# main.net
KiCad netlist of a schematic drawn in EAGLE
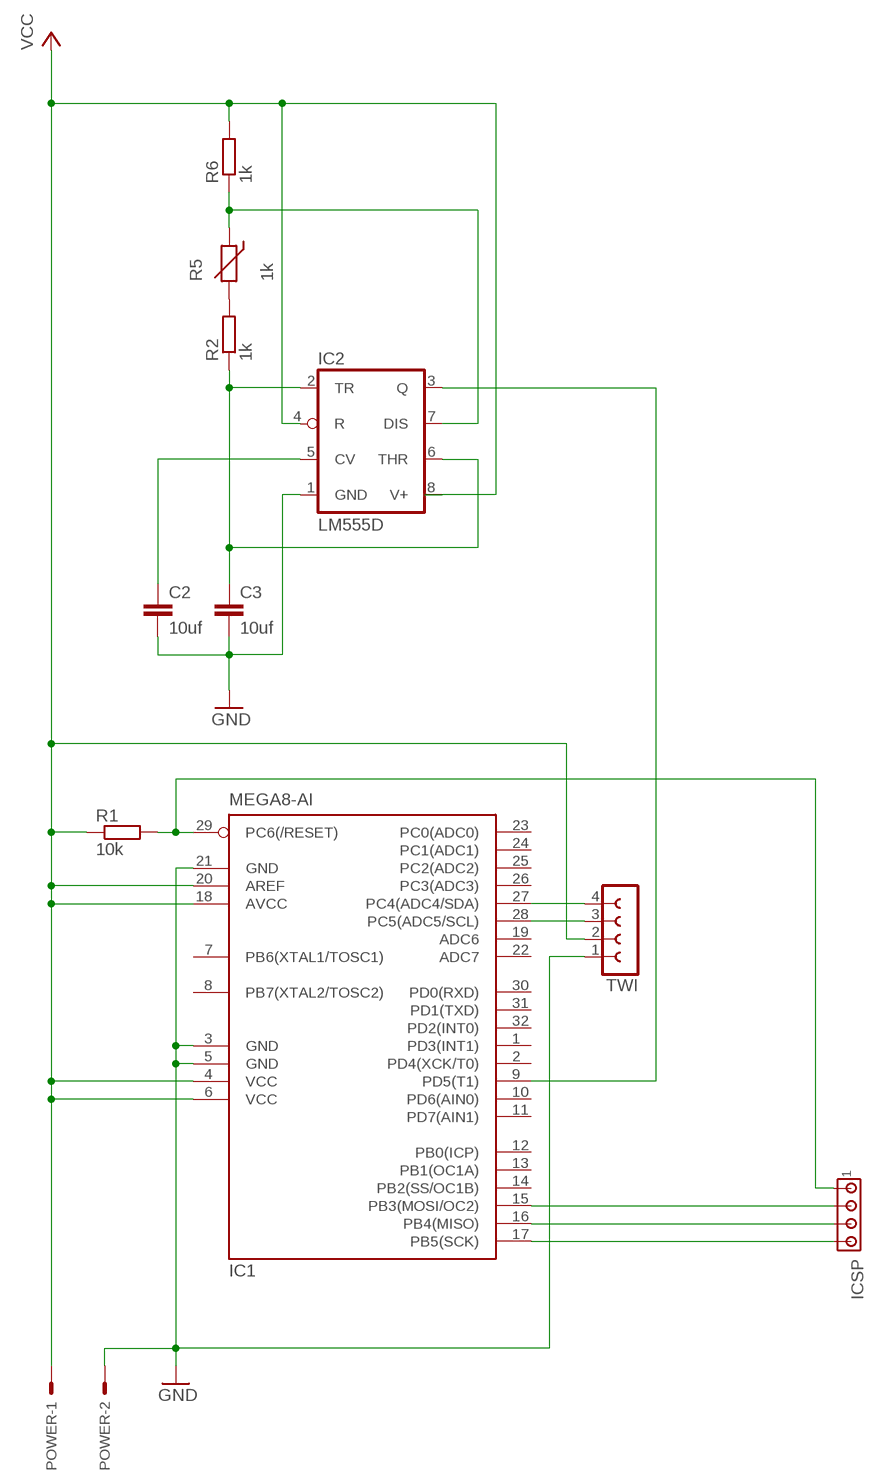
[diagram p0: schematic, sheet 1]

(export (version "E")
  (design (tool "Eeschema 10.0.6"))
  (components
    (comp (ref "C2")
      (value "10uf")
      (footprint "eagle-import:C2012")
      (libsource (lib "eagle-import") (part "C-EUC2012"))
    )
    (comp (ref "C3")
      (value "10uf")
      (footprint "eagle-import:C2012")
      (libsource (lib "eagle-import") (part "C-EUC2012"))
    )
    (comp (ref "IC1")
      (value "MEGA8-AI")
      (footprint "eagle-import:TQFP32-08")
      (fields (field (name "MPN") "ATMEGA8-16AU"))
      (libsource (lib "eagle-import") (part "MEGA8-AI"))
    )
    (comp (ref "IC2")
      (value "LM555D")
      (footprint "eagle-import:SO08")
      (libsource (lib "eagle-import") (part "555DLM"))
    )
    (comp (ref "ICSP")
      (value "MTA04-100")
      (footprint "eagle-import:10X04MTA")
      (libsource (lib "eagle-import") (part "MTA04-100"))
    )
    (comp (ref "POWER")
      (value "332-02")
      (footprint "eagle-import:332-02")
      (libsource (lib "eagle-import") (part "332-02"))
    )
    (comp (ref "R1")
      (value "10k")
      (footprint "eagle-import:0204_7")
      (libsource (lib "eagle-import") (part "R-EU_0204/7"))
    )
    (comp (ref "R2")
      (value "1k")
      (footprint "eagle-import:M2012")
      (libsource (lib "eagle-import") (part "R-EU_M2012"))
    )
    (comp (ref "R5")
      (value "1k")
      (footprint "eagle-import:RS-2,5")
      (libsource (lib "eagle-import") (part "THERMISTOR-2,5"))
    )
    (comp (ref "R6")
      (value "1k")
      (footprint "eagle-import:M2012")
      (libsource (lib "eagle-import") (part "R-EU_M2012"))
    )
    (comp (ref "TWI")
      (value "SPB4")
      (footprint "eagle-import:SPB4")
      (libsource (lib "eagle-import") (part "SPB4"))
    )
  )
  (nets
    (net (code "1") (name "GND") (class "Default")
      (node (ref "C2") (pin "2") (pinfunction "2_2") (pintype "passive"))
      (node (ref "C3") (pin "2") (pinfunction "2_2") (pintype "passive"))
      (node (ref "IC1") (pin "21") (pinfunction "GND_21") (pintype "power_in"))
      (node (ref "IC1") (pin "3") (pinfunction "GND_3") (pintype "power_in"))
      (node (ref "IC1") (pin "5") (pinfunction "GND_5") (pintype "power_in"))
      (node (ref "IC2") (pin "1") (pinfunction "GND_1") (pintype "power_in"))
      (node (ref "POWER") (pin "2") (pinfunction "S_2") (pintype "passive"))
      (node (ref "TWI") (pin "1") (pinfunction "1_1") (pintype "passive"))
    )
    (net (code "2") (name "Net-(IC1-PB3(MOSI{slash}OC2))") (class "Default")
      (node (ref "IC1") (pin "15") (pinfunction "PB3(MOSI/OC2)_15") (pintype "bidirectional"))
      (node (ref "ICSP") (pin "2") (pinfunction "2_2") (pintype "passive"))
    )
    (net (code "3") (name "Net-(IC1-PB4(MISO))") (class "Default")
      (node (ref "IC1") (pin "16") (pinfunction "PB4(MISO)_16") (pintype "bidirectional"))
      (node (ref "ICSP") (pin "3") (pinfunction "3_3") (pintype "passive"))
    )
    (net (code "4") (name "Net-(IC1-PB5(SCK))") (class "Default")
      (node (ref "IC1") (pin "17") (pinfunction "PB5(SCK)_17") (pintype "bidirectional"))
      (node (ref "ICSP") (pin "4") (pinfunction "4_4") (pintype "passive"))
    )
    (net (code "5") (name "Net-(IC1-PC4(ADC4{slash}SDA))") (class "Default")
      (node (ref "IC1") (pin "27") (pinfunction "PC4(ADC4/SDA)_27") (pintype "bidirectional"))
      (node (ref "TWI") (pin "4") (pinfunction "4_4") (pintype "passive"))
    )
    (net (code "6") (name "Net-(IC1-PC5(ADC5{slash}SCL))") (class "Default")
      (node (ref "IC1") (pin "28") (pinfunction "PC5(ADC5/SCL)_28") (pintype "bidirectional"))
      (node (ref "TWI") (pin "3") (pinfunction "3_3") (pintype "passive"))
    )
    (net (code "7") (name "Net-(IC1-PC6({slash}RESET))") (class "Default")
      (node (ref "IC1") (pin "29") (pinfunction "PC6(/RESET)_29") (pintype "bidirectional"))
      (node (ref "ICSP") (pin "1") (pinfunction "1_1") (pintype "passive"))
      (node (ref "R1") (pin "2") (pinfunction "2_2") (pintype "passive"))
    )
    (net (code "8") (name "Net-(IC1-PD5(T1))") (class "Default")
      (node (ref "IC1") (pin "9") (pinfunction "PD5(T1)_9") (pintype "bidirectional"))
      (node (ref "IC2") (pin "3") (pinfunction "Q_3") (pintype "output"))
    )
    (net (code "9") (name "Net-(IC2-CV)") (class "Default")
      (node (ref "C2") (pin "1") (pinfunction "1_1") (pintype "passive"))
      (node (ref "IC2") (pin "5") (pinfunction "CV_5") (pintype "input"))
    )
    (net (code "10") (name "Net-(IC2-DIS)") (class "Default")
      (node (ref "IC2") (pin "7") (pinfunction "DIS_7") (pintype "input"))
      (node (ref "R5") (pin "1") (pinfunction "1_1") (pintype "passive"))
      (node (ref "R6") (pin "1") (pinfunction "1_1") (pintype "passive"))
    )
    (net (code "11") (name "Net-(IC2-THR)") (class "Default")
      (node (ref "C3") (pin "1") (pinfunction "1_1") (pintype "passive"))
      (node (ref "IC2") (pin "2") (pinfunction "TR_2") (pintype "input"))
      (node (ref "IC2") (pin "6") (pinfunction "THR_6") (pintype "input"))
      (node (ref "R2") (pin "1") (pinfunction "1_1") (pintype "passive"))
    )
    (net (code "12") (name "Net-(R2-Pad2)") (class "Default")
      (node (ref "R2") (pin "2") (pinfunction "2_2") (pintype "passive"))
      (node (ref "R5") (pin "2") (pinfunction "2_2") (pintype "passive"))
    )
    (net (code "13") (name "VCC") (class "Default")
      (node (ref "IC1") (pin "18") (pinfunction "AVCC_18") (pintype "power_in"))
      (node (ref "IC1") (pin "20") (pinfunction "AREF_20") (pintype "passive"))
      (node (ref "IC1") (pin "4") (pinfunction "VCC_4") (pintype "power_in"))
      (node (ref "IC1") (pin "6") (pinfunction "VCC_6") (pintype "power_in"))
      (node (ref "IC2") (pin "4") (pinfunction "R_4") (pintype "input"))
      (node (ref "IC2") (pin "8") (pinfunction "V+_8") (pintype "power_in"))
      (node (ref "POWER") (pin "1") (pinfunction "S_1") (pintype "passive"))
      (node (ref "R1") (pin "1") (pinfunction "1_1") (pintype "passive"))
      (node (ref "R6") (pin "2") (pinfunction "2_2") (pintype "passive"))
      (node (ref "TWI") (pin "2") (pinfunction "2_2") (pintype "passive"))
    )
    (net (code "14") (name "unconnected-(IC1-ADC6-Pad19)") (class "Default")
      (node (ref "IC1") (pin "19") (pinfunction "ADC6_19") (pintype "bidirectional"))
    )
    (net (code "15") (name "unconnected-(IC1-ADC7-Pad22)") (class "Default")
      (node (ref "IC1") (pin "22") (pinfunction "ADC7_22") (pintype "bidirectional"))
    )
    (net (code "16") (name "unconnected-(IC1-PB0(ICP)-Pad12)") (class "Default")
      (node (ref "IC1") (pin "12") (pinfunction "PB0(ICP)_12") (pintype "bidirectional"))
    )
    (net (code "17") (name "unconnected-(IC1-PB1(OC1A)-Pad13)") (class "Default")
      (node (ref "IC1") (pin "13") (pinfunction "PB1(OC1A)_13") (pintype "bidirectional"))
    )
    (net (code "18") (name "unconnected-(IC1-PB2(SS{slash}OC1B)-Pad14)") (class "Default")
      (node (ref "IC1") (pin "14") (pinfunction "PB2(SS/OC1B)_14") (pintype "bidirectional"))
    )
    (net (code "19") (name "unconnected-(IC1-PB6(XTAL1{slash}TOSC1)-Pad7)") (class "Default")
      (node (ref "IC1") (pin "7") (pinfunction "PB6(XTAL1/TOSC1)_7") (pintype "bidirectional"))
    )
    (net (code "20") (name "unconnected-(IC1-PB7(XTAL2{slash}TOSC2)-Pad8)") (class "Default")
      (node (ref "IC1") (pin "8") (pinfunction "PB7(XTAL2/TOSC2)_8") (pintype "bidirectional"))
    )
    (net (code "21") (name "unconnected-(IC1-PC0(ADC0)-Pad23)") (class "Default")
      (node (ref "IC1") (pin "23") (pinfunction "PC0(ADC0)_23") (pintype "bidirectional"))
    )
    (net (code "22") (name "unconnected-(IC1-PC1(ADC1)-Pad24)") (class "Default")
      (node (ref "IC1") (pin "24") (pinfunction "PC1(ADC1)_24") (pintype "bidirectional"))
    )
    (net (code "23") (name "unconnected-(IC1-PC2(ADC2)-Pad25)") (class "Default")
      (node (ref "IC1") (pin "25") (pinfunction "PC2(ADC2)_25") (pintype "bidirectional"))
    )
    (net (code "24") (name "unconnected-(IC1-PC3(ADC3)-Pad26)") (class "Default")
      (node (ref "IC1") (pin "26") (pinfunction "PC3(ADC3)_26") (pintype "bidirectional"))
    )
    (net (code "25") (name "unconnected-(IC1-PD0(RXD)-Pad30)") (class "Default")
      (node (ref "IC1") (pin "30") (pinfunction "PD0(RXD)_30") (pintype "bidirectional"))
    )
    (net (code "26") (name "unconnected-(IC1-PD1(TXD)-Pad31)") (class "Default")
      (node (ref "IC1") (pin "31") (pinfunction "PD1(TXD)_31") (pintype "bidirectional"))
    )
    (net (code "27") (name "unconnected-(IC1-PD2(INT0)-Pad32)") (class "Default")
      (node (ref "IC1") (pin "32") (pinfunction "PD2(INT0)_32") (pintype "bidirectional"))
    )
    (net (code "28") (name "unconnected-(IC1-PD3(INT1)-Pad1)") (class "Default")
      (node (ref "IC1") (pin "1") (pinfunction "PD3(INT1)_1") (pintype "bidirectional"))
    )
    (net (code "29") (name "unconnected-(IC1-PD4(XCK{slash}T0)-Pad2)") (class "Default")
      (node (ref "IC1") (pin "2") (pinfunction "PD4(XCK/T0)_2") (pintype "bidirectional"))
    )
    (net (code "30") (name "unconnected-(IC1-PD6(AIN0)-Pad10)") (class "Default")
      (node (ref "IC1") (pin "10") (pinfunction "PD6(AIN0)_10") (pintype "bidirectional"))
    )
    (net (code "31") (name "unconnected-(IC1-PD7(AIN1)-Pad11)") (class "Default")
      (node (ref "IC1") (pin "11") (pinfunction "PD7(AIN1)_11") (pintype "bidirectional"))
    )
  )
)
